# ESP8266_breadboard.net
KiCad netlist of a schematic drawn in EAGLE
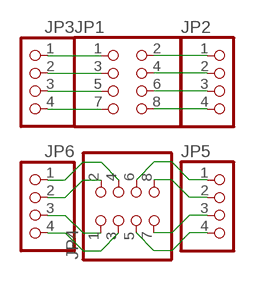
[diagram p0: schematic, sheet 1]

(export (version "E")
  (design (tool "Eeschema 10.0.6"))
  (components
    (comp (ref "JP1")
      (value "PINHD-2X4")
      (footprint "eagle-import:2X04")
      (libsource (lib "eagle-import") (part "PINHD-2X4"))
    )
    (comp (ref "JP2")
      (value "PINHD-1X4")
      (footprint "eagle-import:1X04")
      (libsource (lib "eagle-import") (part "PINHD-1X4"))
    )
    (comp (ref "JP3")
      (value "PINHD-1X4")
      (footprint "eagle-import:1X04")
      (libsource (lib "eagle-import") (part "PINHD-1X4"))
    )
    (comp (ref "JP4")
      (value "PINHD-2X4")
      (footprint "eagle-import:2X04")
      (libsource (lib "eagle-import") (part "PINHD-2X4"))
    )
    (comp (ref "JP5")
      (value "PINHD-1X4")
      (footprint "eagle-import:1X04")
      (libsource (lib "eagle-import") (part "PINHD-1X4"))
    )
    (comp (ref "JP6")
      (value "PINHD-1X4")
      (footprint "eagle-import:1X04")
      (libsource (lib "eagle-import") (part "PINHD-1X4"))
    )
  )
  (nets
    (net (code "1") (name "Net-(JP1-Pad1)") (class "Default")
      (node (ref "JP1") (pin "1") (pinfunction "1_1") (pintype "passive"))
      (node (ref "JP3") (pin "1") (pinfunction "1_1") (pintype "passive"))
    )
    (net (code "2") (name "Net-(JP1-Pad2)") (class "Default")
      (node (ref "JP1") (pin "2") (pinfunction "2_2") (pintype "passive"))
      (node (ref "JP2") (pin "1") (pinfunction "1_1") (pintype "passive"))
    )
    (net (code "3") (name "Net-(JP1-Pad3)") (class "Default")
      (node (ref "JP1") (pin "3") (pinfunction "3_3") (pintype "passive"))
      (node (ref "JP3") (pin "2") (pinfunction "2_2") (pintype "passive"))
    )
    (net (code "4") (name "Net-(JP1-Pad4)") (class "Default")
      (node (ref "JP1") (pin "4") (pinfunction "4_4") (pintype "passive"))
      (node (ref "JP2") (pin "2") (pinfunction "2_2") (pintype "passive"))
    )
    (net (code "5") (name "Net-(JP1-Pad5)") (class "Default")
      (node (ref "JP1") (pin "5") (pinfunction "5_5") (pintype "passive"))
      (node (ref "JP3") (pin "3") (pinfunction "3_3") (pintype "passive"))
    )
    (net (code "6") (name "Net-(JP1-Pad6)") (class "Default")
      (node (ref "JP1") (pin "6") (pinfunction "6_6") (pintype "passive"))
      (node (ref "JP2") (pin "3") (pinfunction "3_3") (pintype "passive"))
    )
    (net (code "7") (name "Net-(JP1-Pad7)") (class "Default")
      (node (ref "JP1") (pin "7") (pinfunction "7_7") (pintype "passive"))
      (node (ref "JP3") (pin "4") (pinfunction "4_4") (pintype "passive"))
    )
    (net (code "8") (name "Net-(JP1-Pad8)") (class "Default")
      (node (ref "JP1") (pin "8") (pinfunction "8_8") (pintype "passive"))
      (node (ref "JP2") (pin "4") (pinfunction "4_4") (pintype "passive"))
    )
    (net (code "9") (name "Net-(JP4-Pad1)") (class "Default")
      (node (ref "JP4") (pin "1") (pinfunction "1_1") (pintype "passive"))
      (node (ref "JP6") (pin "3") (pinfunction "3_3") (pintype "passive"))
    )
    (net (code "10") (name "Net-(JP4-Pad2)") (class "Default")
      (node (ref "JP4") (pin "2") (pinfunction "2_2") (pintype "passive"))
      (node (ref "JP6") (pin "2") (pinfunction "2_2") (pintype "passive"))
    )
    (net (code "11") (name "Net-(JP4-Pad3)") (class "Default")
      (node (ref "JP4") (pin "3") (pinfunction "3_3") (pintype "passive"))
      (node (ref "JP6") (pin "4") (pinfunction "4_4") (pintype "passive"))
    )
    (net (code "12") (name "Net-(JP4-Pad4)") (class "Default")
      (node (ref "JP4") (pin "4") (pinfunction "4_4") (pintype "passive"))
      (node (ref "JP6") (pin "1") (pinfunction "1_1") (pintype "passive"))
    )
    (net (code "13") (name "Net-(JP4-Pad5)") (class "Default")
      (node (ref "JP4") (pin "5") (pinfunction "5_5") (pintype "passive"))
      (node (ref "JP5") (pin "4") (pinfunction "4_4") (pintype "passive"))
    )
    (net (code "14") (name "Net-(JP4-Pad6)") (class "Default")
      (node (ref "JP4") (pin "6") (pinfunction "6_6") (pintype "passive"))
      (node (ref "JP5") (pin "1") (pinfunction "1_1") (pintype "passive"))
    )
    (net (code "15") (name "Net-(JP4-Pad7)") (class "Default")
      (node (ref "JP4") (pin "7") (pinfunction "7_7") (pintype "passive"))
      (node (ref "JP5") (pin "3") (pinfunction "3_3") (pintype "passive"))
    )
    (net (code "16") (name "Net-(JP4-Pad8)") (class "Default")
      (node (ref "JP4") (pin "8") (pinfunction "8_8") (pintype "passive"))
      (node (ref "JP5") (pin "2") (pinfunction "2_2") (pintype "passive"))
    )
  )
)
